# USB.net
KiCad netlist of a schematic drawn in Altium Designer
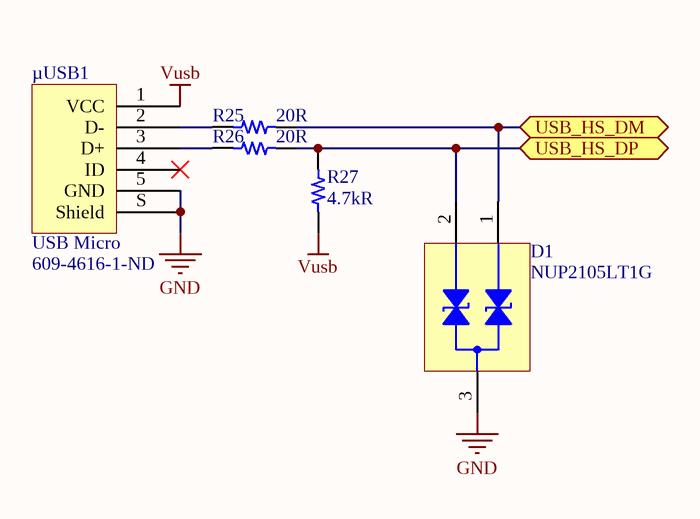
[diagram p0: USB.SchDoc]

(export (version "E")
  (design (tool "Eeschema 10.0.6"))
  (components
    (comp (ref "D1")
      (value "NUP2105LT1G")
      (footprint "ON SEMI SOT-23-3")
      (description "TVS DIODE 24V 44V SOT23-3")
      (fields (field (name "MANUFACTURER") "ON Semiconductor"))
      (libsource (lib "Celestial Altium Library - altium_library") (part "ON SEMI SOT-23-3"))
    )
    (comp (ref "R25")
      (value "20R")
      (footprint "RES 0603/1608")
      (description "Ceramic, SMT Capacitor")
      (fields
        (field (name "MANUFACTURER") "Panasonic")
        (field (name "MANUFACTURER PART NUMBER") "ERJ3EKF20R0V")
      )
      (libsource (lib "yildizIoT Library") (part "Resistor_Chip"))
    )
    (comp (ref "R26")
      (value "20R")
      (footprint "RES 0603/1608")
      (description "Ceramic, SMT Capacitor")
      (fields
        (field (name "MANUFACTURER") "Panasonic")
        (field (name "MANUFACTURER PART NUMBER") "ERJ3EKF20R0V")
      )
      (libsource (lib "yildizIoT Library") (part "Resistor_Chip"))
    )
    (comp (ref "R27")
      (value "4.7kR")
      (footprint "RES 0603/1608")
      (description "Ceramic, SMT Capacitor")
      (fields
        (field (name "MANUFACTURER") "Yageo Phycomp")
        (field (name "MANUFACTURER PART NUMBER") "RC0603FR-074K7L")
      )
      (libsource (lib "yildizIoT Library") (part "Resistor_Chip"))
    )
    (comp (ref "µUSB1")
      (value "USB Micro")
      (footprint "FCI USB 10118193-0001LF")
      (fields
        (field (name "SUPPLIER PART NUMBER 1") "609-4616-1-ND")
        (field (name "MANUFACTURER") "Amphenol FCI")
        (field (name "MANUFACTURER PART NUMBER") "10118193-0001LF")
      )
      (libsource (lib "yildizIoT Library") (part "USB 2.0 Type B Micro"))
    )
  )
  (nets
    (net (code "1") (name "/USB_HS_DM") (class "Default")
      (node (ref "D1") (pin "1") (pinfunction "I/O_1_1") (pintype "passive"))
      (node (ref "R25") (pin "1") (pinfunction "1_1") (pintype "passive"))
    )
    (net (code "2") (name "/USB_HS_DP") (class "Default")
      (node (ref "D1") (pin "2") (pinfunction "GND_2") (pintype "passive"))
      (node (ref "R26") (pin "1") (pinfunction "1_1") (pintype "passive"))
      (node (ref "R27") (pin "2") (pinfunction "2_2") (pintype "passive"))
    )
    (net (code "3") (name "GND") (class "Default")
      (node (ref "D1") (pin "3") (pinfunction "I/O_2_3") (pintype "passive"))
      (node (ref "µUSB1") (pin "5") (pinfunction "GND_5") (pintype "passive"))
      (node (ref "µUSB1") (pin "S") (pinfunction "Shield_S") (pintype "passive"))
    )
    (net (code "4") (name "Net-(µUSB1-D+)") (class "Default")
      (node (ref "R26") (pin "2") (pinfunction "2_2") (pintype "passive"))
      (node (ref "µUSB1") (pin "3") (pinfunction "D+_3") (pintype "passive"))
    )
    (net (code "5") (name "Net-(µUSB1-D-)") (class "Default")
      (node (ref "R25") (pin "2") (pinfunction "2_2") (pintype "passive"))
      (node (ref "µUSB1") (pin "2") (pinfunction "D-_2") (pintype "passive"))
    )
    (net (code "6") (name "Vusb") (class "Default")
      (node (ref "R27") (pin "1") (pinfunction "1_1") (pintype "passive"))
      (node (ref "µUSB1") (pin "1") (pinfunction "VCC_1") (pintype "passive"))
    )
    (net (code "7") (name "unconnected-(µUSB1-ID-Pad4)") (class "Default")
      (node (ref "µUSB1") (pin "4") (pinfunction "ID_4") (pintype "passive+no_connect"))
    )
  )
)
